# touringmach2.net
KiCad netlist of a schematic drawn in EAGLE
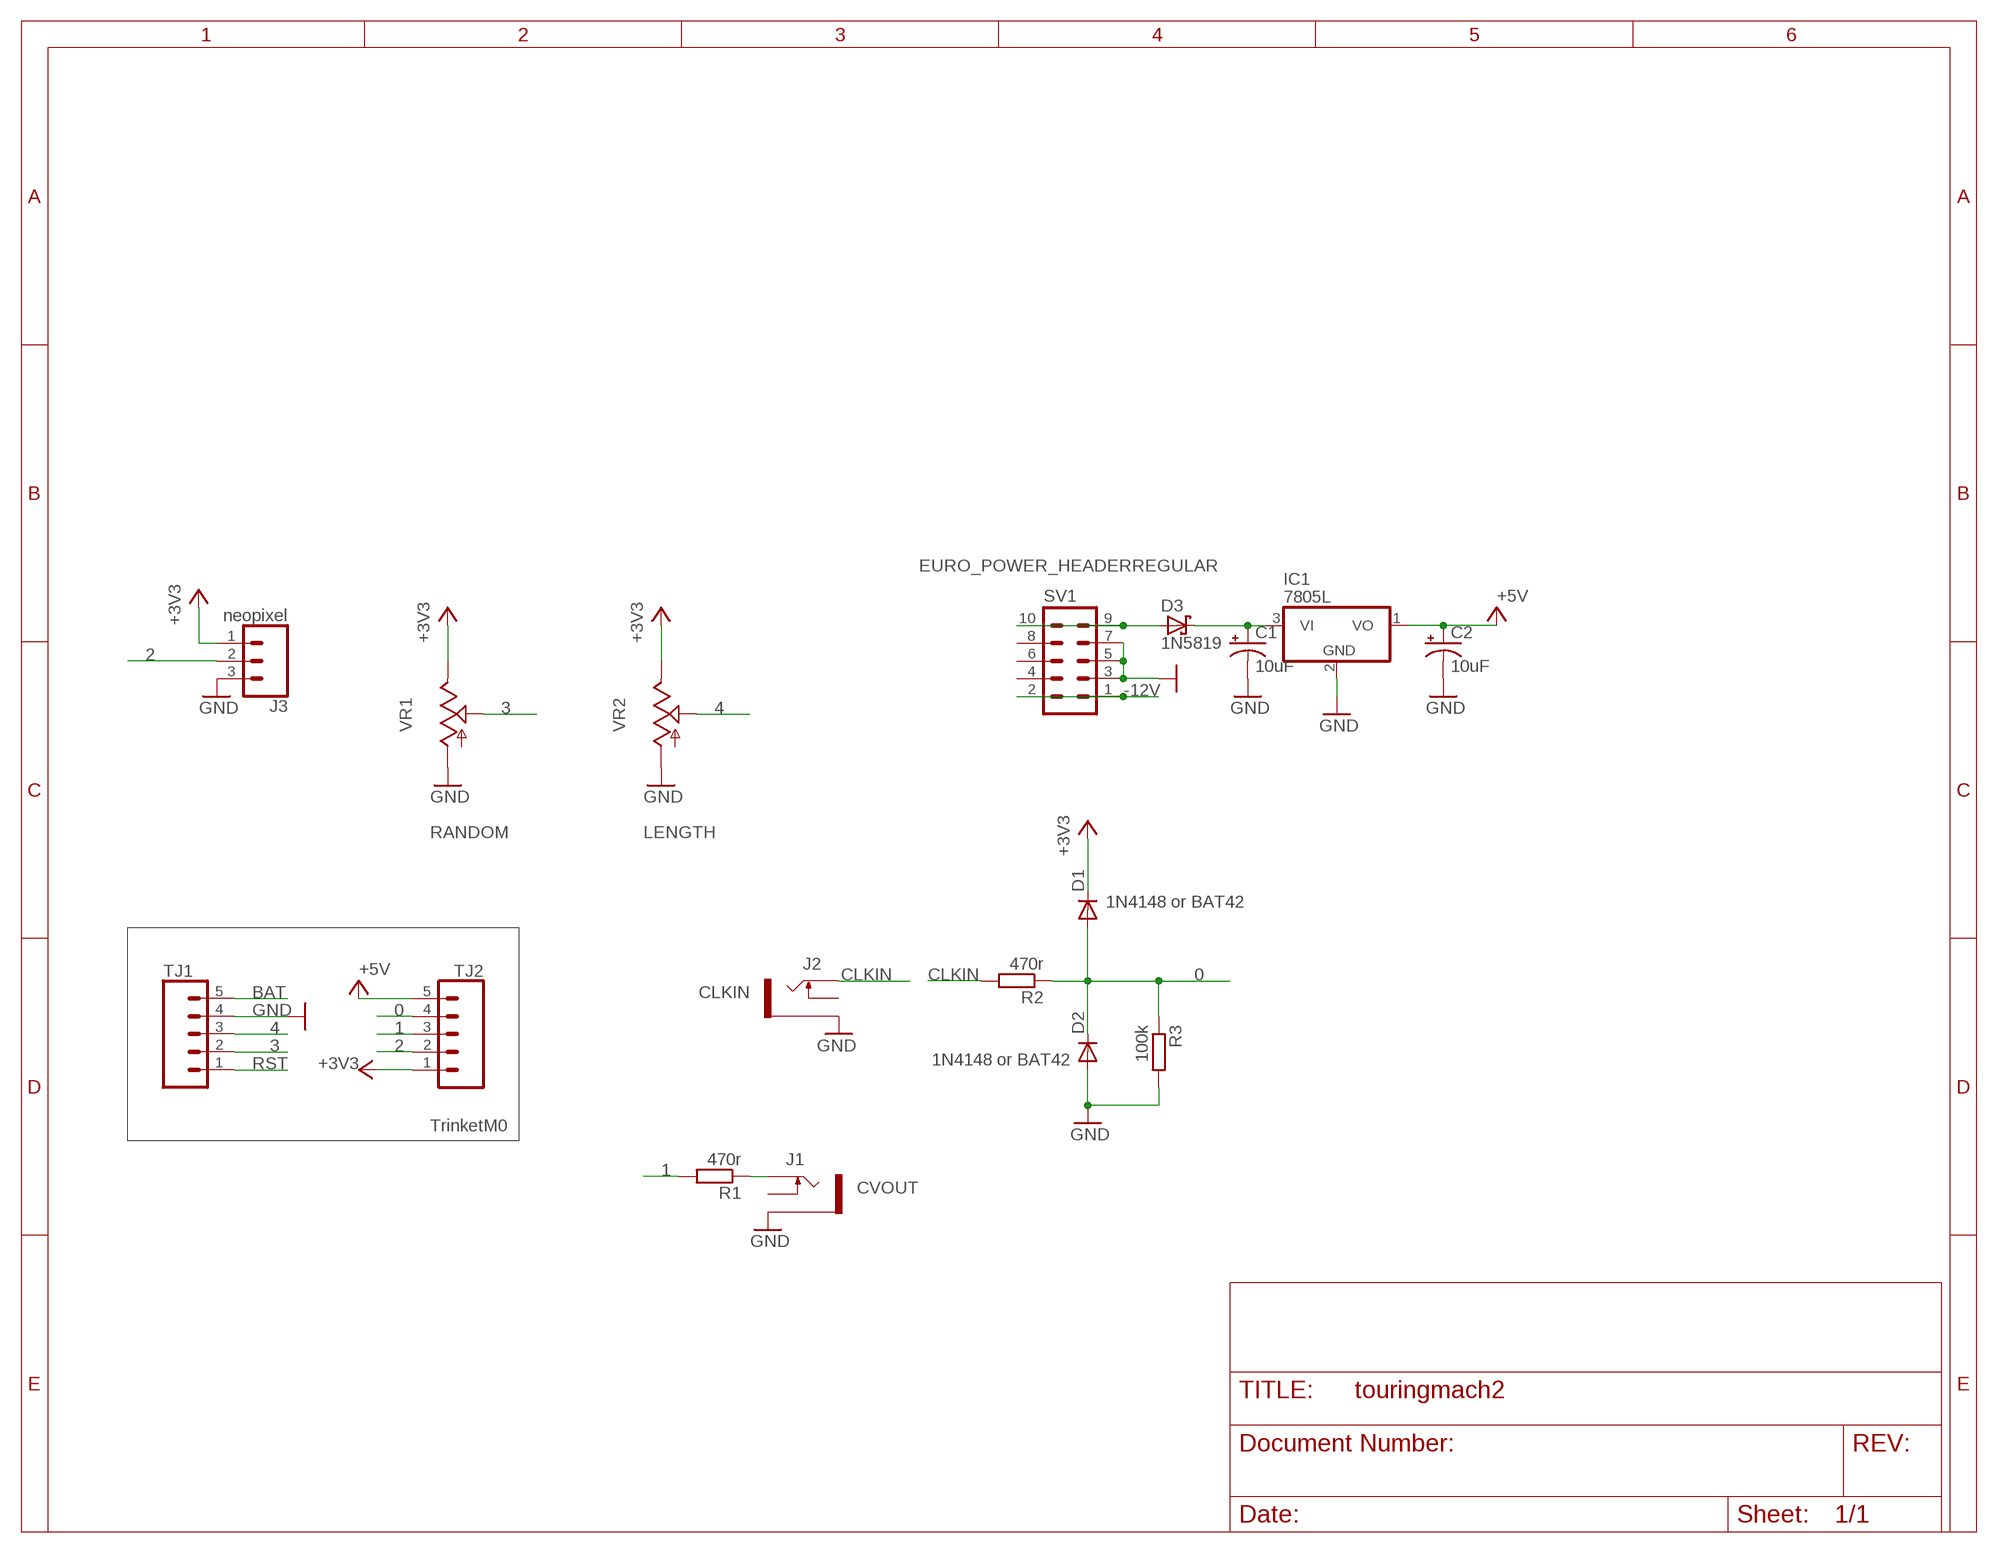
[diagram p0: schematic, sheet 1]

(export (version "E")
  (design (tool "Eeschema 10.0.6"))
  (components
    (comp (ref "C1")
      (value "10uF")
      (footprint "eagle-import:E2,5-6")
      (libsource (lib "eagle-import") (part "CPOL-USE2.5-6"))
    )
    (comp (ref "C2")
      (value "10uF")
      (footprint "eagle-import:E2,5-6")
      (libsource (lib "eagle-import") (part "CPOL-USE2.5-6"))
    )
    (comp (ref "D1")
      (value "1N4148 or BAT42")
      (footprint "eagle-import:DO34-7")
      (libsource (lib "eagle-import") (part "BAT42"))
    )
    (comp (ref "D2")
      (value "1N4148 or BAT42")
      (footprint "eagle-import:DO34-7")
      (libsource (lib "eagle-import") (part "BAT42"))
    )
    (comp (ref "D3")
      (value "1N5819")
      (footprint "eagle-import:DO41-7.6")
      (libsource (lib "eagle-import") (part "1N5819-B"))
    )
    (comp (ref "IC1")
      (value "7805L")
      (footprint "eagle-import:TO92")
      (libsource (lib "eagle-import") (part "78L05"))
    )
    (comp (ref "J1")
      (value "THONKICONNOLD")
      (footprint "eagle-import:THONKICONN")
      (libsource (lib "eagle-import") (part "THONKICONNOLD"))
    )
    (comp (ref "J2")
      (value "THONKICONNOLD")
      (footprint "eagle-import:THONKICONN")
      (libsource (lib "eagle-import") (part "THONKICONNOLD"))
    )
    (comp (ref "J3")
      (value "neopixel")
      (footprint "eagle-import:1X03")
      (libsource (lib "eagle-import") (part "CONN_03"))
    )
    (comp (ref "R1")
      (value "470r")
      (footprint "eagle-import:7MM_RESISTOR")
      (libsource (lib "eagle-import") (part "RESISTOR7MM"))
    )
    (comp (ref "R2")
      (value "470r")
      (footprint "eagle-import:7MM_RESISTOR")
      (libsource (lib "eagle-import") (part "RESISTOR7MM"))
    )
    (comp (ref "R3")
      (value "100k")
      (footprint "eagle-import:7MM_RESISTOR")
      (libsource (lib "eagle-import") (part "RESISTOR7MM"))
    )
    (comp (ref "SV1")
      (value "EURO_POWER_HEADERREGULAR")
      (footprint "eagle-import:EURO_POWER_HEADER")
      (libsource (lib "eagle-import") (part "EURO_POWER_HEADERREGULAR"))
    )
    (comp (ref "TJ1")
      (value "CONN_05")
      (footprint "eagle-import:1X05")
      (libsource (lib "eagle-import") (part "CONN_05"))
    )
    (comp (ref "TJ2")
      (value "CONN_05")
      (footprint "eagle-import:1X05")
      (libsource (lib "eagle-import") (part "CONN_05"))
    )
    (comp (ref "VR1")
      (value "9MM_SNAP-IN_POT_")
      (footprint "eagle-import:9MM_SNAP-IN_POT")
      (libsource (lib "eagle-import") (part "9MM_SNAP-IN_POT_"))
    )
    (comp (ref "VR2")
      (value "9MM_SNAP-IN_POT_")
      (footprint "eagle-import:9MM_SNAP-IN_POT")
      (libsource (lib "eagle-import") (part "9MM_SNAP-IN_POT_"))
    )
  )
  (nets
    (net (code "1") (name "+3V3") (class "Default")
      (node (ref "D1") (pin "C") (pinfunction "C_C") (pintype "passive"))
      (node (ref "J3") (pin "1") (pinfunction "1_1") (pintype "passive"))
      (node (ref "TJ2") (pin "1") (pinfunction "1_1") (pintype "passive"))
      (node (ref "VR1") (pin "3") (pinfunction "E_3") (pintype "passive"))
      (node (ref "VR2") (pin "3") (pinfunction "E_3") (pintype "passive"))
    )
    (net (code "2") (name "+5V") (class "Default")
      (node (ref "C2") (pin "+") (pinfunction "+_+") (pintype "passive"))
      (node (ref "IC1") (pin "1") (pinfunction "VO_1") (pintype "passive"))
      (node (ref "TJ2") (pin "5") (pinfunction "5_5") (pintype "passive"))
    )
    (net (code "3") (name "/-12V") (class "Default")
      (node (ref "SV1") (pin "1") (pinfunction "1_1") (pintype "passive"))
      (node (ref "SV1") (pin "2") (pinfunction "2_2") (pintype "passive"))
    )
    (net (code "4") (name "/0") (class "Default")
      (node (ref "D1") (pin "A") (pinfunction "A_A") (pintype "passive"))
      (node (ref "D2") (pin "C") (pinfunction "C_C") (pintype "passive"))
      (node (ref "R2") (pin "1") (pinfunction "1_1") (pintype "passive"))
      (node (ref "R3") (pin "1") (pinfunction "1_1") (pintype "passive"))
      (node (ref "TJ2") (pin "4") (pinfunction "4_4") (pintype "passive"))
    )
    (net (code "5") (name "/1") (class "Default")
      (node (ref "R1") (pin "2") (pinfunction "2_2") (pintype "passive"))
      (node (ref "TJ2") (pin "3") (pinfunction "3_3") (pintype "passive"))
    )
    (net (code "6") (name "/2") (class "Default")
      (node (ref "J3") (pin "2") (pinfunction "2_2") (pintype "passive"))
      (node (ref "TJ2") (pin "2") (pinfunction "2_2") (pintype "passive"))
    )
    (net (code "7") (name "/3") (class "Default")
      (node (ref "TJ1") (pin "2") (pinfunction "2_2") (pintype "passive"))
      (node (ref "VR1") (pin "2") (pinfunction "S_2") (pintype "passive"))
    )
    (net (code "8") (name "/4") (class "Default")
      (node (ref "TJ1") (pin "3") (pinfunction "3_3") (pintype "passive"))
      (node (ref "VR2") (pin "2") (pinfunction "S_2") (pintype "passive"))
    )
    (net (code "9") (name "/BAT") (class "Default")
      (node (ref "TJ1") (pin "5") (pinfunction "5_5") (pintype "passive"))
    )
    (net (code "10") (name "/CLKIN") (class "Default")
      (node (ref "J2") (pin "P$3_TIP") (pinfunction "TIP_P$3_TIP") (pintype "passive"))
      (node (ref "R2") (pin "2") (pinfunction "2_2") (pintype "passive"))
    )
    (net (code "11") (name "/RST") (class "Default")
      (node (ref "TJ1") (pin "1") (pinfunction "1_1") (pintype "passive"))
    )
    (net (code "12") (name "GND") (class "Default")
      (node (ref "C1") (pin "-") (pinfunction "-_-") (pintype "passive"))
      (node (ref "C2") (pin "-") (pinfunction "-_-") (pintype "passive"))
      (node (ref "D2") (pin "A") (pinfunction "A_A") (pintype "passive"))
      (node (ref "IC1") (pin "2") (pinfunction "GND_2") (pintype "passive"))
      (node (ref "J1") (pin "P$1_SLEEVE") (pinfunction "SLEEVE_P$1_SLEEVE") (pintype "passive"))
      (node (ref "J2") (pin "P$1_SLEEVE") (pinfunction "SLEEVE_P$1_SLEEVE") (pintype "passive"))
      (node (ref "J3") (pin "3") (pinfunction "3_3") (pintype "passive"))
      (node (ref "R3") (pin "2") (pinfunction "2_2") (pintype "passive"))
      (node (ref "SV1") (pin "3") (pinfunction "3_3") (pintype "passive"))
      (node (ref "SV1") (pin "5") (pinfunction "5_5") (pintype "passive"))
      (node (ref "SV1") (pin "7") (pinfunction "7_7") (pintype "passive"))
      (node (ref "TJ1") (pin "4") (pinfunction "4_4") (pintype "passive"))
      (node (ref "VR1") (pin "1") (pinfunction "A_1") (pintype "passive"))
      (node (ref "VR2") (pin "1") (pinfunction "A_1") (pintype "passive"))
    )
    (net (code "13") (name "Net-(D3-PadA)") (class "Default")
      (node (ref "D3") (pin "A") (pinfunction "A_A") (pintype "passive"))
      (node (ref "SV1") (pin "10") (pinfunction "10_10") (pintype "passive"))
      (node (ref "SV1") (pin "9") (pinfunction "9_9") (pintype "passive"))
    )
    (net (code "14") (name "Net-(IC1-VI)") (class "Default")
      (node (ref "C1") (pin "+") (pinfunction "+_+") (pintype "passive"))
      (node (ref "D3") (pin "C") (pinfunction "C_C") (pintype "passive"))
      (node (ref "IC1") (pin "3") (pinfunction "VI_3") (pintype "input"))
    )
    (net (code "15") (name "Net-(J1-TIP)") (class "Default")
      (node (ref "J1") (pin "P$3_TIP") (pinfunction "TIP_P$3_TIP") (pintype "passive"))
      (node (ref "R1") (pin "1") (pinfunction "1_1") (pintype "passive"))
    )
    (net (code "16") (name "unconnected-(J1-SWITCH-PadP$2_SWITCH)") (class "Default")
      (node (ref "J1") (pin "P$2_SWITCH") (pinfunction "SWITCH_P$2_SWITCH") (pintype "passive"))
    )
    (net (code "17") (name "unconnected-(J2-SWITCH-PadP$2_SWITCH)") (class "Default")
      (node (ref "J2") (pin "P$2_SWITCH") (pinfunction "SWITCH_P$2_SWITCH") (pintype "passive"))
    )
    (net (code "18") (name "unconnected-(SV1-Pad4)") (class "Default")
      (node (ref "SV1") (pin "4") (pinfunction "4_4") (pintype "passive"))
    )
    (net (code "19") (name "unconnected-(SV1-Pad6)") (class "Default")
      (node (ref "SV1") (pin "6") (pinfunction "6_6") (pintype "passive"))
    )
    (net (code "20") (name "unconnected-(SV1-Pad8)") (class "Default")
      (node (ref "SV1") (pin "8") (pinfunction "8_8") (pintype "passive"))
    )
  )
)
